# 3_-STM32F103_debugger.net
KiCad netlist of a schematic drawn in Altium Designer
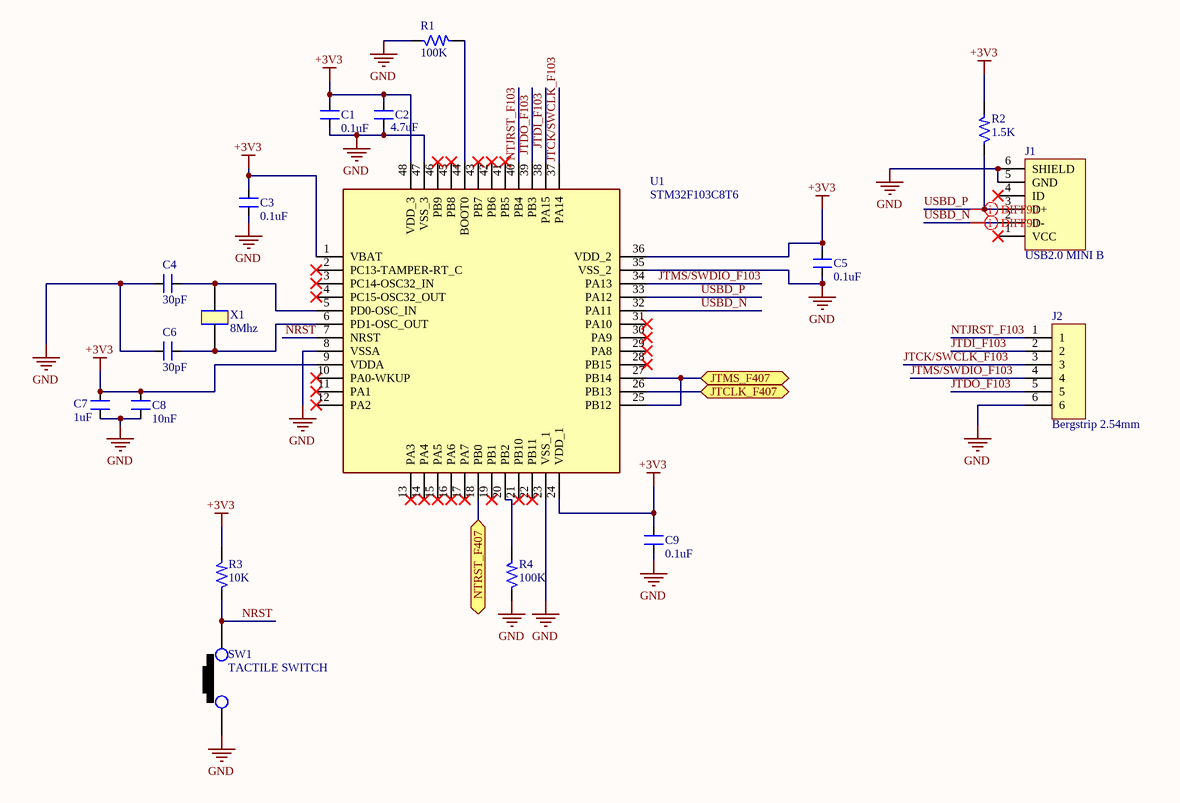
[diagram p0: [3]-STM32F103_debugger.SchDoc]

(export (version "E")
  (design (tool "Eeschema 10.0.6"))
  (components
    (comp (ref "C1")
      (value "0.1uF")
      (footprint "CAP_0805")
      (description "0.1µF ±10% 50V Ceramic Capacitor X7R 0805 (2012 Metric)")
      (fields
        (field (name "MANUFACTURER") "Samsung")
        (field (name "MANUFACTURER PART NUMBER") "CL21B104KBCNNNC")
      )
      (libsource (lib "ESTEEMPCBLIB") (part "CAP_0.1uF-50V-10%-0805"))
    )
    (comp (ref "C2")
      (value "4.7uF")
      (footprint "CAP_0805")
      (description "4.7µF ±10% 50V Ceramic Capacitor X5R 0805 (2012 Metric)")
      (fields
        (field (name "MANUFACTURER") "Yageo")
        (field (name "MANUFACTURER PART NUMBER") "GRM21BR61H475KE51L")
      )
      (libsource (lib "ESTEEMPCBLIB") (part "CAP_4.7uF-50V-10%-0805"))
    )
    (comp (ref "C3")
      (value "0.1uF")
      (footprint "CAP_0805")
      (description "0.1µF ±10% 50V Ceramic Capacitor X7R 0805 (2012 Metric)")
      (fields
        (field (name "MANUFACTURER") "Samsung")
        (field (name "MANUFACTURER PART NUMBER") "CL21B104KBCNNNC")
      )
      (libsource (lib "ESTEEMPCBLIB") (part "CAP_0.1uF-50V-10%-0805"))
    )
    (comp (ref "C4")
      (value "30pF")
      (footprint "CAP_0805")
      (description "±10% 50V Ceramic Capacitor C0G, NP0 0805 (2012 Metric)")
      (fields
        (field (name "MANUFACTURER PART NUMBER") "C0805C300K5GAC7800")
        (field (name "MANUFACTURER") "KEMET")
      )
      (libsource (lib "ESTEEMPCBLIB") (part "CAP_30pF-50V-10%-0805"))
    )
    (comp (ref "C5")
      (value "0.1uF")
      (footprint "CAP_0805")
      (description "0.1µF ±10% 50V Ceramic Capacitor X7R 0805 (2012 Metric)")
      (fields
        (field (name "MANUFACTURER") "Samsung")
        (field (name "MANUFACTURER PART NUMBER") "CL21B104KBCNNNC")
      )
      (libsource (lib "ESTEEMPCBLIB") (part "CAP_0.1uF-50V-10%-0805"))
    )
    (comp (ref "C6")
      (value "30pF")
      (footprint "CAP_0805")
      (description "±10% 50V Ceramic Capacitor C0G, NP0 0805 (2012 Metric)")
      (fields
        (field (name "MANUFACTURER PART NUMBER") "C0805C300K5GAC7800")
        (field (name "MANUFACTURER") "KEMET")
      )
      (libsource (lib "ESTEEMPCBLIB") (part "CAP_30pF-50V-10%-0805"))
    )
    (comp (ref "C7")
      (value "1uF")
      (footprint "CAP_0805")
      (description "1µF ±5% 50V Ceramic Capacitor X7R 0805 (2012 Metric)")
      (fields
        (field (name "MANUFACTURER") "Samsung")
        (field (name "MANUFACTURER PART NUMBER") "CC0805JKX7R9BB105")
      )
      (libsource (lib "ESTEEMPCBLIB") (part "CAP_1uF-50V-5%-0805"))
    )
    (comp (ref "C8")
      (value "10nF")
      (footprint "CAP_0805")
      (description "10000pF ±10% 50V Ceramic Capacitor X7R 0805 (2012 Metric)")
      (fields
        (field (name "MANUFACTURER") "Samsung")
        (field (name "MANUFACTURER PART NUMBER") "C0805C103K5RECAUTO")
      )
      (libsource (lib "ESTEEMPCBLIB") (part "CAP_10nF-50V-10%-0805"))
    )
    (comp (ref "C9")
      (value "0.1uF")
      (footprint "CAP_0805")
      (description "0.1µF ±10% 50V Ceramic Capacitor X7R 0805 (2012 Metric)")
      (fields
        (field (name "MANUFACTURER") "Samsung")
        (field (name "MANUFACTURER PART NUMBER") "CL21B104KBCNNNC")
      )
      (libsource (lib "ESTEEMPCBLIB") (part "CAP_0.1uF-50V-10%-0805"))
    )
    (comp (ref "J1")
      (value "USB2.0 MINI B")
      (footprint "CON_690-005-299-043")
      (description "USB - mini B USB 2.0 Receptacle Connector 5 Position Surface Mount, Right Angle")
      (fields
        (field (name "MANUFACTURER") "EDAC")
        (field (name "MANUFACTURER PART NUMBER") "690-005-299-043")
      )
      (libsource (lib "ESTEEMPCBLIB") (part "CON_USB2.0-MINIB-SMD"))
    )
    (comp (ref "J2")
      (value "Bergstrip 2.54mm")
      (footprint "CON6_100_59D78_TH_ST")
      (description "6 Pins, 1 Row 2.54mm Pitch, Straight bergstrip, Female")
      (fields (field (name "MANUFACTURER") "Molex") (field (name "MANUFACTURER PART NUMBER") "22-10-2061"))
      (libsource (lib "ESTEEMPCBLIB") (part "CON-BS-SKT_6X1-100-ST-TH"))
    )
    (comp (ref "R1")
      (value "100K")
      (footprint "RES_0603")
      (description "100 kOhms ±1% 0.1W, 1/10W Chip Resistor 0603 (1608 Metric) Automotive AEC-Q200 Thick Film")
      (fields
        (field (name "MANUFACTURER") "Stackpole Electronics")
        (field (name "MANUFACTURER PART NUMBER") "RMCF0603FT100K")
      )
      (libsource (lib "ESTEEMPCBLIB") (part "RES_100K-0.1W-1%-0603"))
    )
    (comp (ref "R2")
      (value "1.5K")
      (footprint "RES_0805")
      (description "1.5 kOhms ±1% 0.125W, 1/8W Chip Resistor 0805 (2012 Metric) Thick Film")
      (fields
        (field (name "MANUFACTURER") "TE Connectivity Passive Product")
        (field (name "MANUFACTURER PART NUMBER") "CRG0805F1K5")
      )
      (libsource (lib "ESTEEMPCBLIB") (part "RES_1.5K-0.125W-1%-0805"))
    )
    (comp (ref "R3")
      (value "10K")
      (footprint "RES_0603")
      (description "10 kOhms ±1% 0.1W, 1/10W Chip Resistor 0603 (1608 Metric) Automotive AEC-Q200 Thick Film")
      (fields (field (name "MANUFACTURER") "Walsin") (field (name "MANUFACTURER PART NUMBER") "WR06X1002FTL"))
      (libsource (lib "ESTEEMPCBLIB") (part "RES_10K-0.1W-1%-0603"))
    )
    (comp (ref "R4")
      (value "100K")
      (footprint "RES_0603")
      (description "100 kOhms ±1% 0.1W, 1/10W Chip Resistor 0603 (1608 Metric) Automotive AEC-Q200 Thick Film")
      (fields
        (field (name "MANUFACTURER") "Stackpole Electronics")
        (field (name "MANUFACTURER PART NUMBER") "RMCF0603FT100K")
      )
      (libsource (lib "ESTEEMPCBLIB") (part "RES_100K-0.1W-1%-0603"))
    )
    (comp (ref "SW1")
      (value "TACTILE SWITCH")
      (footprint "SW_342_SMD")
      (description "Tactile Switch SPST-NO Top Actuated Surface Mount")
      (fields
        (field (name "MANUFACTURER") "ITT C&K")
        (field (name "MANUFACTURER PART NUMBER") "RS-282G05A3-SMRT")
      )
      (libsource (lib "ESTEEMPCBLIB") (part "SW1_RS-282G05A3-SMRT-SMD"))
    )
    (comp (ref "U1")
      (value "STM32F103C8T6")
      (footprint "LQFP-48_19.6_393_58X11_SMD")
      (description "ARM® Cortex®-M3 STM32F1 Microcontroller IC 32-Bit 72MHz 64KB (64K x 8) FLASH 48-LQFP (7x7)")
      (fields (field (name "MANUFACTURER") "STMicroelectronics"))
      (libsource (lib "ESTEEMPCBLIB") (part "IC_STM32F103C8T6"))
    )
    (comp (ref "X1")
      (value "8Mhz")
      (footprint "XTAL_314_240X47_SMD")
      (description "8MHz ±30ppm Crystal 32pF 60 Ohms HC-49/US")
      (fields
        (field (name "MANUFACTURER") "Fox Electronics")
        (field (name "MANUFACTURER PART NUMBER") "ECS-80-32-5PX-TR")
      )
      (libsource (lib "ESTEEMPCBLIB") (part "XTAL_8MHZ-ECS-80-32-5PX-SMD"))
    )
  )
  (nets
    (net (code "1") (name "+3V3") (class "Default")
      (node (ref "C1") (pin "2") (pinfunction "2_2") (pintype "passive"))
      (node (ref "C2") (pin "2") (pinfunction "2_2") (pintype "passive"))
      (node (ref "C3") (pin "2") (pinfunction "2_2") (pintype "passive"))
      (node (ref "C5") (pin "2") (pinfunction "2_2") (pintype "passive"))
      (node (ref "C7") (pin "2") (pinfunction "2_2") (pintype "passive"))
      (node (ref "C8") (pin "2") (pinfunction "2_2") (pintype "passive"))
      (node (ref "C9") (pin "2") (pinfunction "2_2") (pintype "passive"))
      (node (ref "R2") (pin "2") (pinfunction "2_2") (pintype "passive"))
      (node (ref "R3") (pin "2") (pinfunction "2_2") (pintype "passive"))
      (node (ref "U1") (pin "1") (pinfunction "VBAT_1") (pintype "passive"))
      (node (ref "U1") (pin "24") (pinfunction "VDD_1_24") (pintype "passive"))
      (node (ref "U1") (pin "36") (pinfunction "VDD_2_36") (pintype "passive"))
      (node (ref "U1") (pin "48") (pinfunction "VDD_3_48") (pintype "passive"))
      (node (ref "U1") (pin "9") (pinfunction "VDDA_9") (pintype "passive"))
    )
    (net (code "2") (name "/JTCK{slash}SWCLK_F103") (class "Default")
      (node (ref "J2") (pin "3") (pinfunction "3_3") (pintype "passive"))
      (node (ref "U1") (pin "37") (pinfunction "PA14_37") (pintype "passive"))
    )
    (net (code "3") (name "/JTCLK_F407") (class "Default")
      (node (ref "U1") (pin "26") (pinfunction "PB13_26") (pintype "passive"))
    )
    (net (code "4") (name "/JTDI_F103") (class "Default")
      (node (ref "J2") (pin "2") (pinfunction "2_2") (pintype "passive"))
      (node (ref "U1") (pin "38") (pinfunction "PA15_38") (pintype "passive"))
    )
    (net (code "5") (name "/JTDO_F103") (class "Default")
      (node (ref "J2") (pin "5") (pinfunction "5_5") (pintype "passive"))
      (node (ref "U1") (pin "39") (pinfunction "PB3_39") (pintype "passive"))
    )
    (net (code "6") (name "/JTMS_F407") (class "Default")
      (node (ref "U1") (pin "25") (pinfunction "PB12_25") (pintype "passive"))
      (node (ref "U1") (pin "27") (pinfunction "PB14_27") (pintype "passive"))
    )
    (net (code "7") (name "/JTMS{slash}SWDIO_F103") (class "Default")
      (node (ref "J2") (pin "4") (pinfunction "4_4") (pintype "passive"))
      (node (ref "U1") (pin "34") (pinfunction "PA13_34") (pintype "passive"))
    )
    (net (code "8") (name "/NRST") (class "Default")
      (node (ref "R3") (pin "1") (pinfunction "1_1") (pintype "passive"))
      (node (ref "SW1") (pin "2") (pinfunction "2_2") (pintype "passive"))
      (node (ref "U1") (pin "7") (pinfunction "NRST_7") (pintype "passive"))
    )
    (net (code "9") (name "/NTJRST_F103") (class "Default")
      (node (ref "J2") (pin "1") (pinfunction "1_1") (pintype "passive"))
      (node (ref "U1") (pin "40") (pinfunction "PB4_40") (pintype "passive"))
    )
    (net (code "10") (name "/NTRST_F407") (class "Default")
      (node (ref "U1") (pin "18") (pinfunction "PB0_18") (pintype "passive"))
    )
    (net (code "11") (name "/USBD_N") (class "Default")
      (node (ref "J1") (pin "2") (pinfunction "D-_2") (pintype "passive"))
      (node (ref "U1") (pin "32") (pinfunction "PA11_32") (pintype "passive"))
    )
    (net (code "12") (name "/USBD_P") (class "Default")
      (node (ref "J1") (pin "3") (pinfunction "D+_3") (pintype "passive"))
      (node (ref "R2") (pin "1") (pinfunction "1_1") (pintype "passive"))
      (node (ref "U1") (pin "33") (pinfunction "PA12_33") (pintype "passive"))
    )
    (net (code "13") (name "GND") (class "Default")
      (node (ref "C1") (pin "1") (pinfunction "1_1") (pintype "passive"))
      (node (ref "C2") (pin "1") (pinfunction "1_1") (pintype "passive"))
      (node (ref "C3") (pin "1") (pinfunction "1_1") (pintype "passive"))
      (node (ref "C4") (pin "1") (pinfunction "1_1") (pintype "passive"))
      (node (ref "C5") (pin "1") (pinfunction "1_1") (pintype "passive"))
      (node (ref "C6") (pin "1") (pinfunction "1_1") (pintype "passive"))
      (node (ref "C7") (pin "1") (pinfunction "1_1") (pintype "passive"))
      (node (ref "C8") (pin "1") (pinfunction "1_1") (pintype "passive"))
      (node (ref "C9") (pin "1") (pinfunction "1_1") (pintype "passive"))
      (node (ref "J1") (pin "5") (pinfunction "GND_5") (pintype "passive"))
      (node (ref "J1") (pin "6") (pinfunction "SHIELD_6") (pintype "passive"))
      (node (ref "J2") (pin "6") (pinfunction "6_6") (pintype "passive"))
      (node (ref "R1") (pin "1") (pinfunction "1_1") (pintype "passive"))
      (node (ref "R4") (pin "1") (pinfunction "1_1") (pintype "passive"))
      (node (ref "SW1") (pin "1") (pinfunction "1_1") (pintype "passive"))
      (node (ref "U1") (pin "23") (pinfunction "VSS_1_23") (pintype "passive"))
      (node (ref "U1") (pin "35") (pinfunction "VSS_2_35") (pintype "passive"))
      (node (ref "U1") (pin "47") (pinfunction "VSS_3_47") (pintype "passive"))
      (node (ref "U1") (pin "8") (pinfunction "VSSA_8") (pintype "passive"))
    )
    (net (code "14") (name "Net-(U1-BOOT0)") (class "Default")
      (node (ref "R1") (pin "2") (pinfunction "2_2") (pintype "passive"))
      (node (ref "U1") (pin "44") (pinfunction "BOOT0_44") (pintype "passive"))
    )
    (net (code "15") (name "Net-(U1-PB2)") (class "Default")
      (node (ref "R4") (pin "2") (pinfunction "2_2") (pintype "passive"))
      (node (ref "U1") (pin "20") (pinfunction "PB2_20") (pintype "passive"))
    )
    (net (code "16") (name "Net-(U1-PD0-OSC_IN)") (class "Default")
      (node (ref "C4") (pin "2") (pinfunction "2_2") (pintype "passive"))
      (node (ref "U1") (pin "5") (pinfunction "PD0-OSC_IN_5") (pintype "passive"))
      (node (ref "X1") (pin "2") (pinfunction "2_2") (pintype "passive"))
    )
    (net (code "17") (name "Net-(U1-PD1-OSC_OUT)") (class "Default")
      (node (ref "C6") (pin "2") (pinfunction "2_2") (pintype "passive"))
      (node (ref "U1") (pin "6") (pinfunction "PD1-OSC_OUT_6") (pintype "passive"))
      (node (ref "X1") (pin "1") (pinfunction "1_1") (pintype "passive"))
    )
    (net (code "18") (name "unconnected-(J1-ID-Pad4)") (class "Default")
      (node (ref "J1") (pin "4") (pinfunction "ID_4") (pintype "passive+no_connect"))
    )
    (net (code "19") (name "unconnected-(J1-VCC-Pad1)") (class "Default")
      (node (ref "J1") (pin "1") (pinfunction "VCC_1") (pintype "passive+no_connect"))
    )
    (net (code "20") (name "unconnected-(U1-PA0-WKUP-Pad10)") (class "Default")
      (node (ref "U1") (pin "10") (pinfunction "PA0-WKUP_10") (pintype "passive+no_connect"))
    )
    (net (code "21") (name "unconnected-(U1-PA1-Pad11)") (class "Default")
      (node (ref "U1") (pin "11") (pinfunction "PA1_11") (pintype "passive+no_connect"))
    )
    (net (code "22") (name "unconnected-(U1-PA2-Pad12)") (class "Default")
      (node (ref "U1") (pin "12") (pinfunction "PA2_12") (pintype "passive+no_connect"))
    )
    (net (code "23") (name "unconnected-(U1-PA3-Pad13)") (class "Default")
      (node (ref "U1") (pin "13") (pinfunction "PA3_13") (pintype "passive+no_connect"))
    )
    (net (code "24") (name "unconnected-(U1-PA4-Pad14)") (class "Default")
      (node (ref "U1") (pin "14") (pinfunction "PA4_14") (pintype "passive+no_connect"))
    )
    (net (code "25") (name "unconnected-(U1-PA5-Pad15)") (class "Default")
      (node (ref "U1") (pin "15") (pinfunction "PA5_15") (pintype "passive+no_connect"))
    )
    (net (code "26") (name "unconnected-(U1-PA6-Pad16)") (class "Default")
      (node (ref "U1") (pin "16") (pinfunction "PA6_16") (pintype "passive+no_connect"))
    )
    (net (code "27") (name "unconnected-(U1-PA7-Pad17)") (class "Default")
      (node (ref "U1") (pin "17") (pinfunction "PA7_17") (pintype "passive+no_connect"))
    )
    (net (code "28") (name "unconnected-(U1-PA8-Pad29)") (class "Default")
      (node (ref "U1") (pin "29") (pinfunction "PA8_29") (pintype "passive+no_connect"))
    )
    (net (code "29") (name "unconnected-(U1-PA9-Pad30)") (class "Default")
      (node (ref "U1") (pin "30") (pinfunction "PA9_30") (pintype "passive+no_connect"))
    )
    (net (code "30") (name "unconnected-(U1-PA10-Pad31)") (class "Default")
      (node (ref "U1") (pin "31") (pinfunction "PA10_31") (pintype "passive+no_connect"))
    )
    (net (code "31") (name "unconnected-(U1-PB1-Pad19)") (class "Default")
      (node (ref "U1") (pin "19") (pinfunction "PB1_19") (pintype "passive+no_connect"))
    )
    (net (code "32") (name "unconnected-(U1-PB5-Pad41)") (class "Default")
      (node (ref "U1") (pin "41") (pinfunction "PB5_41") (pintype "passive+no_connect"))
    )
    (net (code "33") (name "unconnected-(U1-PB6-Pad42)") (class "Default")
      (node (ref "U1") (pin "42") (pinfunction "PB6_42") (pintype "passive+no_connect"))
    )
    (net (code "34") (name "unconnected-(U1-PB7-Pad43)") (class "Default")
      (node (ref "U1") (pin "43") (pinfunction "PB7_43") (pintype "passive+no_connect"))
    )
    (net (code "35") (name "unconnected-(U1-PB8-Pad45)") (class "Default")
      (node (ref "U1") (pin "45") (pinfunction "PB8_45") (pintype "passive+no_connect"))
    )
    (net (code "36") (name "unconnected-(U1-PB9-Pad46)") (class "Default")
      (node (ref "U1") (pin "46") (pinfunction "PB9_46") (pintype "passive+no_connect"))
    )
    (net (code "37") (name "unconnected-(U1-PB10-Pad21)") (class "Default")
      (node (ref "U1") (pin "21") (pinfunction "PB10_21") (pintype "passive+no_connect"))
    )
    (net (code "38") (name "unconnected-(U1-PB11-Pad22)") (class "Default")
      (node (ref "U1") (pin "22") (pinfunction "PB11_22") (pintype "passive+no_connect"))
    )
    (net (code "39") (name "unconnected-(U1-PB15-Pad28)") (class "Default")
      (node (ref "U1") (pin "28") (pinfunction "PB15_28") (pintype "passive+no_connect"))
    )
    (net (code "40") (name "unconnected-(U1-PC13-TAMPER-RT_C-Pad2)") (class "Default")
      (node (ref "U1") (pin "2") (pinfunction "PC13-TAMPER-RT_C_2") (pintype "passive+no_connect"))
    )
    (net (code "41") (name "unconnected-(U1-PC14-OSC32_IN-Pad3)") (class "Default")
      (node (ref "U1") (pin "3") (pinfunction "PC14-OSC32_IN_3") (pintype "passive+no_connect"))
    )
    (net (code "42") (name "unconnected-(U1-PC15-OSC32_OUT-Pad4)") (class "Default")
      (node (ref "U1") (pin "4") (pinfunction "PC15-OSC32_OUT_4") (pintype "passive+no_connect"))
    )
  )
)
